# Logging_Controller.net
KiCad netlist of a schematic drawn in EAGLE
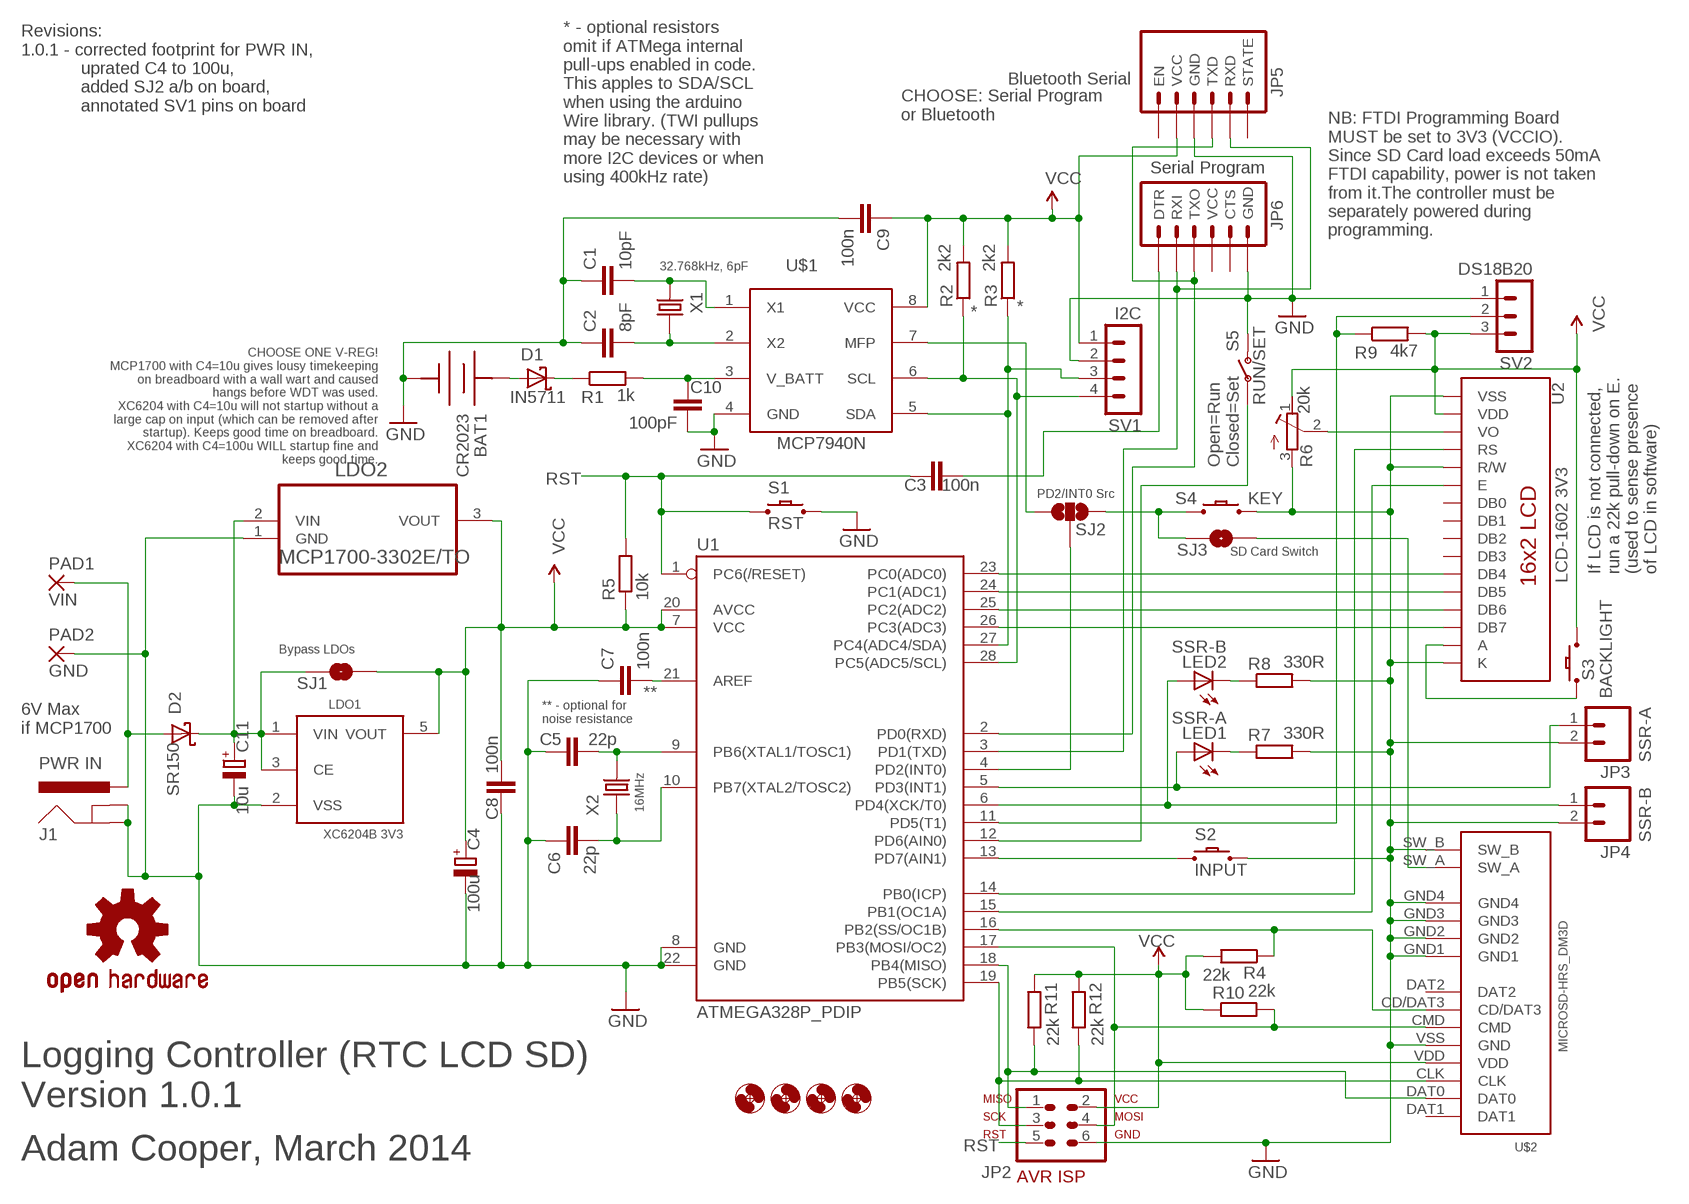
[diagram p0: schematic, sheet 1]

(export (version "E")
  (design (tool "Eeschema 10.0.6"))
  (components
    (comp (ref "BAT1")
      (value "CR2023")
      (footprint "eagle-import:KEYSTONE3003")
      (libsource (lib "eagle-import") (part "COIN-CELLLIR2450-H"))
    )
    (comp (ref "C1")
      (value "10pF")
      (footprint "eagle-import:C025-024X044")
      (libsource (lib "eagle-import") (part "C-EU025-024X044100NF+22PF"))
    )
    (comp (ref "C2")
      (value "8pF")
      (footprint "eagle-import:C025-024X044")
      (libsource (lib "eagle-import") (part "C-EU025-024X044100NF+22PF"))
    )
    (comp (ref "C3")
      (value "100n")
      (footprint "eagle-import:C025-024X044")
      (libsource (lib "eagle-import") (part "C-EU025-024X044100NF+22PF"))
    )
    (comp (ref "C4")
      (value "100u")
      (footprint "eagle-import:E2,5-5")
      (libsource (lib "eagle-import") (part "CPOL-EUE2.5-5"))
    )
    (comp (ref "C5")
      (value "22p")
      (footprint "eagle-import:C025-024X044")
      (libsource (lib "eagle-import") (part "C-EU025-024X044100NF+22PF"))
    )
    (comp (ref "C6")
      (value "22p")
      (footprint "eagle-import:C025-024X044")
      (libsource (lib "eagle-import") (part "C-EU025-024X044100NF+22PF"))
    )
    (comp (ref "C7")
      (value "100n")
      (footprint "eagle-import:C025-024X044")
      (libsource (lib "eagle-import") (part "C-EU025-024X044100NF+22PF"))
    )
    (comp (ref "C8")
      (value "100n")
      (footprint "eagle-import:C025-024X044")
      (libsource (lib "eagle-import") (part "C-EU025-024X044100NF+22PF"))
    )
    (comp (ref "C9")
      (value "100n")
      (footprint "eagle-import:C025-024X044")
      (libsource (lib "eagle-import") (part "C-EU025-024X044100NF+22PF"))
    )
    (comp (ref "C10")
      (value "100pF")
      (footprint "eagle-import:C025-024X044")
      (libsource (lib "eagle-import") (part "C-EU025-024X044100NF+22PF"))
    )
    (comp (ref "C11")
      (value "10u")
      (footprint "eagle-import:E2,5-5")
      (libsource (lib "eagle-import") (part "CPOL-EUE2.5-5"))
    )
    (comp (ref "D1")
      (value "IN5711")
      (footprint "eagle-import:DO35-7")
      (libsource (lib "eagle-import") (part "DIODE-SCHOTTKYDO35-7"))
    )
    (comp (ref "D2")
      (value "SR150")
      (footprint "eagle-import:DO-41")
      (libsource (lib "eagle-import") (part "DIODE-SCHOTTKYDO-41"))
    )
    (comp (ref "H1")
      (value "MOUNT-HOLE3.0_REDUCED")
      (footprint "eagle-import:3,0")
      (libsource (lib "eagle-import") (part "MOUNT-HOLE3.0_REDUCED"))
    )
    (comp (ref "H2")
      (value "MOUNT-HOLE3.0_REDUCED")
      (footprint "eagle-import:3,0")
      (libsource (lib "eagle-import") (part "MOUNT-HOLE3.0_REDUCED"))
    )
    (comp (ref "H3")
      (value "MOUNT-HOLE3.0_REDUCED")
      (footprint "eagle-import:3,0")
      (libsource (lib "eagle-import") (part "MOUNT-HOLE3.0_REDUCED"))
    )
    (comp (ref "H4")
      (value "MOUNT-HOLE3.0_REDUCED")
      (footprint "eagle-import:3,0")
      (libsource (lib "eagle-import") (part "MOUNT-HOLE3.0_REDUCED"))
    )
    (comp (ref "J1")
      (value "PWR IN")
      (footprint "eagle-import:POWER_JACK_SLOT2")
      (libsource (lib "eagle-import") (part "POWER_JACKMJ-179PH"))
    )
    (comp (ref "JP2")
      (value "AVR-ISP")
      (footprint "eagle-import:AVR-ISP-6")
      (libsource (lib "eagle-import") (part "AVR-ISP-6VERT"))
    )
    (comp (ref "JP3")
      (value "SSR-A")
      (footprint "eagle-import:1X02")
      (libsource (lib "eagle-import") (part "M02PTH"))
    )
    (comp (ref "JP4")
      (value "SSR-B")
      (footprint "eagle-import:1X02")
      (libsource (lib "eagle-import") (part "M02PTH"))
    )
    (comp (ref "JP5")
      (value "Bluetooth Serial")
      (footprint "eagle-import:BT_MOD_ROUND")
      (libsource (lib "eagle-import") (part "BLUETOOTH_SERIAL_MODULEBT_MOD_ROUND"))
    )
    (comp (ref "JP6")
      (value "Serial Program")
      (footprint "eagle-import:1X06")
      (libsource (lib "eagle-import") (part "ARDUINO_SERIAL_PROGRAMPTH"))
    )
    (comp (ref "LDO1")
      (value "XC6204B 3V3")
      (footprint "eagle-import:SOT23-5")
      (libsource (lib "eagle-import") (part "XC6204/5"))
    )
    (comp (ref "LDO2")
      (value "MCP1700-3302E/TO")
      (footprint "eagle-import:TO127P254X495-3")
      (libsource (lib "eagle-import") (part "MCP1700-3302E/TO"))
    )
    (comp (ref "LED1")
      (value "SSR-A")
      (footprint "eagle-import:LED5MM")
      (libsource (lib "eagle-import") (part "LED5MM"))
    )
    (comp (ref "LED2")
      (value "SSR-B")
      (footprint "eagle-import:LED5MM")
      (libsource (lib "eagle-import") (part "LED5MM"))
    )
    (comp (ref "LOGO1")
      (value "OSHW-LOGOS")
      (footprint "eagle-import:OSHW-LOGO-S")
      (libsource (lib "eagle-import") (part "OSHW-LOGOS"))
    )
    (comp (ref "PAD1")
      (value "VIN")
      (footprint "eagle-import:2,54_1,1")
      (libsource (lib "eagle-import") (part "WIREPAD2,54/1,1"))
    )
    (comp (ref "PAD2")
      (value "GND")
      (footprint "eagle-import:2,54_1,1")
      (libsource (lib "eagle-import") (part "WIREPAD2,54/1,1"))
    )
    (comp (ref "R1")
      (value "1k")
      (footprint "eagle-import:0204_7")
      (libsource (lib "eagle-import") (part "R-EU_0204/7"))
    )
    (comp (ref "R2")
      (value "2k2")
      (footprint "eagle-import:0204_7")
      (libsource (lib "eagle-import") (part "R-EU_0204/7"))
    )
    (comp (ref "R3")
      (value "2k2")
      (footprint "eagle-import:0204_7")
      (libsource (lib "eagle-import") (part "R-EU_0204/7"))
    )
    (comp (ref "R4")
      (value "22k")
      (footprint "eagle-import:0204_7")
      (libsource (lib "eagle-import") (part "R-EU_0204/7"))
    )
    (comp (ref "R5")
      (value "10k")
      (footprint "eagle-import:0204_7")
      (libsource (lib "eagle-import") (part "R-EU_0204/7"))
    )
    (comp (ref "R6")
      (value "20k")
      (footprint "eagle-import:RTRIMT93YB")
      (libsource (lib "eagle-import") (part "R-TRIMMT93YB"))
    )
    (comp (ref "R7")
      (value "330R")
      (footprint "eagle-import:0204_7")
      (libsource (lib "eagle-import") (part "R-EU_0204/7"))
    )
    (comp (ref "R8")
      (value "330R")
      (footprint "eagle-import:0204_7")
      (libsource (lib "eagle-import") (part "R-EU_0204/7"))
    )
    (comp (ref "R9")
      (value "4k7")
      (footprint "eagle-import:0204_7")
      (libsource (lib "eagle-import") (part "R-EU_0204/7"))
    )
    (comp (ref "R10")
      (value "22k")
      (footprint "eagle-import:0204_7")
      (libsource (lib "eagle-import") (part "R-EU_0204/7"))
    )
    (comp (ref "R11")
      (value "22k")
      (footprint "eagle-import:0204_7")
      (libsource (lib "eagle-import") (part "R-EU_0204/7"))
    )
    (comp (ref "R12")
      (value "22k")
      (footprint "eagle-import:0204_7")
      (libsource (lib "eagle-import") (part "R-EU_0204/7"))
    )
    (comp (ref "S1")
      (value "RST")
      (footprint "eagle-import:TACTILE-PTH")
      (libsource (lib "eagle-import") (part "SWITCH-MOMENTARY-2PTH"))
    )
    (comp (ref "S2")
      (value "INPUT")
      (footprint "eagle-import:OFF_BOARD_SPST")
      (libsource (lib "eagle-import") (part "SWITCH-MOMENTARY-2OFF_BOARD_SPST"))
    )
    (comp (ref "S3")
      (value "BACKLIGHT")
      (footprint "eagle-import:OFF_BOARD_SPST")
      (libsource (lib "eagle-import") (part "SWITCH-MOMENTARY-2OFF_BOARD_SPST"))
    )
    (comp (ref "S4")
      (value "KEY")
      (footprint "eagle-import:OFF_BOARD_SPST")
      (libsource (lib "eagle-import") (part "SWITCH-MOMENTARY-2OFF_BOARD_SPST"))
    )
    (comp (ref "S5")
      (value "RUN/SET")
      (footprint "eagle-import:SWITCH-SPST-OFFBOARD")
      (libsource (lib "eagle-import") (part "SWITCH-SPSTOFFBOARD"))
    )
    (comp (ref "SJ1")
      (value "Bypass LDOs")
      (footprint "eagle-import:SJ_2S-NO")
      (libsource (lib "eagle-import") (part "SOLDERJUMPERNO"))
    )
    (comp (ref "SJ2")
      (value "PD2/INT0 Src")
      (footprint "eagle-import:SJ_3")
      (libsource (lib "eagle-import") (part "SOLDERJUMPER_2WAYS"))
    )
    (comp (ref "SJ3")
      (value "SD Card Switch")
      (footprint "eagle-import:SJ_2S-NO")
      (libsource (lib "eagle-import") (part "SOLDERJUMPERNO"))
    )
    (comp (ref "SV1")
      (value "I2C")
      (footprint "eagle-import:MA04-1")
      (libsource (lib "eagle-import") (part "MA04-1"))
    )
    (comp (ref "SV2")
      (value "DS18B20")
      (footprint "eagle-import:MA03-1")
      (libsource (lib "eagle-import") (part "MA03-1"))
    )
    (comp (ref "U$1")
      (value "MCP7940N")
      (footprint "eagle-import:DIL08")
      (libsource (lib "eagle-import") (part "MCP7940NPDIP"))
    )
    (comp (ref "U$2")
      (value "MICROSD-HRS_DM3D")
      (footprint "eagle-import:DM3D")
      (libsource (lib "eagle-import") (part "MICROSD-HRS_DM3D"))
    )
    (comp (ref "U1")
      (value "ATMEGA328P_PDIP")
      (footprint "eagle-import:DIL28-3@1")
      (libsource (lib "eagle-import") (part "ATMEGA328P_PDIP"))
    )
    (comp (ref "U2")
      (value "LCD-1602 3V3")
      (footprint "eagle-import:LCD-16X2_NOSILK")
      (libsource (lib "eagle-import") (part "LCD-16X2NOSILK"))
    )
    (comp (ref "X1")
      (value "32.768kHz, 6pF")
      (footprint "eagle-import:TC26H")
      (libsource (lib "eagle-import") (part "CRYSTAL-TC26H"))
    )
    (comp (ref "X2")
      (value "16MHz")
      (footprint "eagle-import:HC49U-V")
      (libsource (lib "eagle-import") (part "CRYSTAL-HC49U-V16MHZ"))
    )
  )
  (nets
    (net (code "1") (name "/RST") (class "Default")
      (node (ref "C3") (pin "1") (pinfunction "1_1") (pintype "passive"))
      (node (ref "JP2") (pin "5") (pinfunction "5_5") (pintype "passive"))
      (node (ref "R5") (pin "2") (pinfunction "2_2") (pintype "passive"))
      (node (ref "S1") (pin "1") (pinfunction "1_1") (pintype "passive"))
      (node (ref "U1") (pin "1") (pinfunction "PC6(/RESET)_1") (pintype "bidirectional"))
    )
    (net (code "2") (name "GND") (class "Default")
      (node (ref "BAT1") (pin "NEG") (pinfunction "NEG_NEG") (pintype "bidirectional"))
      (node (ref "C1") (pin "1") (pinfunction "1_1") (pintype "passive"))
      (node (ref "C10") (pin "1") (pinfunction "1_1") (pintype "passive"))
      (node (ref "C11") (pin "-") (pinfunction "-_-") (pintype "passive"))
      (node (ref "C2") (pin "1") (pinfunction "1_1") (pintype "passive"))
      (node (ref "C4") (pin "-") (pinfunction "-_-") (pintype "passive"))
      (node (ref "C5") (pin "1") (pinfunction "1_1") (pintype "passive"))
      (node (ref "C6") (pin "1") (pinfunction "1_1") (pintype "passive"))
      (node (ref "C7") (pin "1") (pinfunction "1_1") (pintype "passive"))
      (node (ref "C8") (pin "1") (pinfunction "1_1") (pintype "passive"))
      (node (ref "C9") (pin "2") (pinfunction "2_2") (pintype "passive"))
      (node (ref "J1") (pin "GND") (pinfunction "GND_GND") (pintype "bidirectional"))
      (node (ref "J1") (pin "GND2") (pinfunction "GNDBREAK_GND2") (pintype "bidirectional"))
      (node (ref "JP2") (pin "6") (pinfunction "6_6") (pintype "passive"))
      (node (ref "JP3") (pin "2") (pinfunction "2_2") (pintype "passive"))
      (node (ref "JP4") (pin "2") (pinfunction "2_2") (pintype "passive"))
      (node (ref "JP5") (pin "4") (pinfunction "GND_4") (pintype "power_in"))
      (node (ref "JP6") (pin "6") (pinfunction "GND_6") (pintype "passive"))
      (node (ref "LDO1") (pin "2") (pinfunction "VSS_2") (pintype "power_in"))
      (node (ref "LDO2") (pin "1") (pinfunction "GND_1") (pintype "passive"))
      (node (ref "PAD2") (pin "1") (pinfunction "P_1") (pintype "passive"))
      (node (ref "R6") (pin "3") (pinfunction "E_3") (pintype "passive"))
      (node (ref "R7") (pin "2") (pinfunction "2_2") (pintype "passive"))
      (node (ref "R8") (pin "2") (pinfunction "2_2") (pintype "passive"))
      (node (ref "S1") (pin "3") (pinfunction "2_3") (pintype "passive"))
      (node (ref "S2") (pin "P$2") (pinfunction "2_P$2") (pintype "passive"))
      (node (ref "S4") (pin "P$2") (pinfunction "2_P$2") (pintype "passive"))
      (node (ref "S5") (pin "1") (pinfunction "O_1") (pintype "passive"))
      (node (ref "SV1") (pin "2") (pinfunction "2_2") (pintype "passive"))
      (node (ref "SV2") (pin "1") (pinfunction "1_1") (pintype "passive"))
      (node (ref "U$1") (pin "4") (pinfunction "GND_4") (pintype "bidirectional"))
      (node (ref "U$2") (pin "GND1") (pinfunction "GND1_GND1") (pintype "bidirectional"))
      (node (ref "U$2") (pin "GND2") (pinfunction "GND2_GND2") (pintype "bidirectional"))
      (node (ref "U$2") (pin "GND3") (pinfunction "GND3_GND3") (pintype "bidirectional"))
      (node (ref "U$2") (pin "GND4") (pinfunction "GND4_GND4") (pintype "bidirectional"))
      (node (ref "U$2") (pin "SW_B") (pinfunction "SW_B_SW_B") (pintype "bidirectional"))
      (node (ref "U$2") (pin "VSS") (pinfunction "GND_VSS") (pintype "bidirectional"))
      (node (ref "U1") (pin "22") (pinfunction "GND_22") (pintype "bidirectional"))
      (node (ref "U1") (pin "8") (pinfunction "GND_8") (pintype "bidirectional"))
      (node (ref "U2") (pin "1") (pinfunction "VSS_1") (pintype "power_in"))
      (node (ref "U2") (pin "16") (pinfunction "K_16") (pintype "power_in"))
      (node (ref "U2") (pin "5") (pinfunction "R/W_5") (pintype "input"))
    )
    (net (code "3") (name "Net-(BAT1-POS-PadPOS1)") (class "Default")
      (node (ref "BAT1") (pin "POS") (pinfunction "POS_POS") (pintype "bidirectional"))
      (node (ref "BAT1") (pin "POS1") (pinfunction "POS_POS1") (pintype "bidirectional"))
      (node (ref "D1") (pin "A") (pinfunction "A_A") (pintype "passive"))
    )
    (net (code "4") (name "Net-(D1-PadC)") (class "Default")
      (node (ref "D1") (pin "C") (pinfunction "C_C") (pintype "passive"))
      (node (ref "R1") (pin "1") (pinfunction "1_1") (pintype "passive"))
    )
    (net (code "5") (name "Net-(J1-PWR)") (class "Default")
      (node (ref "D2") (pin "A") (pinfunction "A_A") (pintype "passive"))
      (node (ref "J1") (pin "POS") (pinfunction "PWR_POS") (pintype "bidirectional"))
      (node (ref "PAD1") (pin "1") (pinfunction "P_1") (pintype "passive"))
    )
    (net (code "6") (name "Net-(JP5-RXD)") (class "Default")
      (node (ref "JP5") (pin "2") (pinfunction "RXD_2") (pintype "input"))
      (node (ref "JP6") (pin "2") (pinfunction "RXI_2") (pintype "passive"))
      (node (ref "U1") (pin "3") (pinfunction "PD1(TXD)_3") (pintype "bidirectional"))
    )
    (net (code "7") (name "Net-(JP5-TXD)") (class "Default")
      (node (ref "JP5") (pin "3") (pinfunction "TXD_3") (pintype "output"))
      (node (ref "JP6") (pin "3") (pinfunction "TXO_3") (pintype "passive"))
      (node (ref "U1") (pin "2") (pinfunction "PD0(RXD)_2") (pintype "bidirectional"))
    )
    (net (code "8") (name "Net-(JP6-DTR)") (class "Default")
      (node (ref "C3") (pin "2") (pinfunction "2_2") (pintype "passive"))
      (node (ref "JP6") (pin "1") (pinfunction "DTR_1") (pintype "passive"))
    )
    (net (code "9") (name "Net-(LDO1-CE)") (class "Default")
      (node (ref "C11") (pin "+") (pinfunction "+_+") (pintype "passive"))
      (node (ref "D2") (pin "C") (pinfunction "C_C") (pintype "passive"))
      (node (ref "LDO1") (pin "1") (pinfunction "VIN_1") (pintype "power_in"))
      (node (ref "LDO1") (pin "3") (pinfunction "CE_3") (pintype "input"))
      (node (ref "LDO2") (pin "2") (pinfunction "VIN_2") (pintype "input"))
      (node (ref "SJ1") (pin "1") (pinfunction "1_1") (pintype "passive"))
    )
    (net (code "10") (name "Net-(LED1-C)") (class "Default")
      (node (ref "LED1") (pin "K") (pinfunction "C_K") (pintype "passive"))
      (node (ref "R7") (pin "1") (pinfunction "1_1") (pintype "passive"))
    )
    (net (code "11") (name "Net-(LED2-C)") (class "Default")
      (node (ref "LED2") (pin "K") (pinfunction "C_K") (pintype "passive"))
      (node (ref "R8") (pin "1") (pinfunction "1_1") (pintype "passive"))
    )
    (net (code "12") (name "Net-(R6-S)") (class "Default")
      (node (ref "R6") (pin "2") (pinfunction "S_2") (pintype "passive"))
      (node (ref "U2") (pin "3") (pinfunction "VO_3") (pintype "bidirectional"))
    )
    (net (code "13") (name "Net-(S2-1)") (class "Default")
      (node (ref "S2") (pin "P$1") (pinfunction "1_P$1") (pintype "passive"))
      (node (ref "U1") (pin "13") (pinfunction "PD7(AIN1)_13") (pintype "bidirectional"))
    )
    (net (code "14") (name "Net-(S3-1)") (class "Default")
      (node (ref "S3") (pin "P$1") (pinfunction "1_P$1") (pintype "passive"))
      (node (ref "U2") (pin "15") (pinfunction "A_15") (pintype "power_in"))
    )
    (net (code "15") (name "Net-(S4-1)") (class "Default")
      (node (ref "S4") (pin "P$1") (pinfunction "1_P$1") (pintype "passive"))
      (node (ref "SJ2") (pin "3") (pinfunction "3_3") (pintype "passive"))
      (node (ref "SJ3") (pin "1") (pinfunction "1_1") (pintype "passive"))
    )
    (net (code "16") (name "Net-(S5-P)") (class "Default")
      (node (ref "S5") (pin "2") (pinfunction "P_2") (pintype "passive"))
      (node (ref "U1") (pin "12") (pinfunction "PD6(AIN0)_12") (pintype "bidirectional"))
    )
    (net (code "17") (name "Net-(SJ3-Pad2)") (class "Default")
      (node (ref "SJ3") (pin "2") (pinfunction "2_2") (pintype "passive"))
      (node (ref "U$2") (pin "SW_A") (pinfunction "SW_A_SW_A") (pintype "bidirectional"))
    )
    (net (code "18") (name "Net-(U$1-MFP)") (class "Default")
      (node (ref "SJ2") (pin "1") (pinfunction "1_1") (pintype "passive"))
      (node (ref "U$1") (pin "7") (pinfunction "MFP_7") (pintype "bidirectional"))
    )
    (net (code "19") (name "Net-(U$1-SCL)") (class "Default")
      (node (ref "R2") (pin "1") (pinfunction "1_1") (pintype "passive"))
      (node (ref "SV1") (pin "4") (pinfunction "4_4") (pintype "passive"))
      (node (ref "U$1") (pin "6") (pinfunction "SCL_6") (pintype "bidirectional"))
      (node (ref "U1") (pin "28") (pinfunction "PC5(ADC5/SCL)_28") (pintype "bidirectional"))
    )
    (net (code "20") (name "Net-(U$1-SDA)") (class "Default")
      (node (ref "R3") (pin "1") (pinfunction "1_1") (pintype "passive"))
      (node (ref "SV1") (pin "3") (pinfunction "3_3") (pintype "passive"))
      (node (ref "U$1") (pin "5") (pinfunction "SDA_5") (pintype "bidirectional"))
      (node (ref "U1") (pin "27") (pinfunction "PC4(ADC4/SDA)_27") (pintype "bidirectional"))
    )
    (net (code "21") (name "Net-(U$1-V_BATT)") (class "Default")
      (node (ref "C10") (pin "2") (pinfunction "2_2") (pintype "passive"))
      (node (ref "R1") (pin "2") (pinfunction "2_2") (pintype "passive"))
      (node (ref "U$1") (pin "3") (pinfunction "V_BATT_3") (pintype "bidirectional"))
    )
    (net (code "22") (name "Net-(U$1-X1)") (class "Default")
      (node (ref "C1") (pin "2") (pinfunction "2_2") (pintype "passive"))
      (node (ref "U$1") (pin "1") (pinfunction "X1_1") (pintype "bidirectional"))
      (node (ref "X1") (pin "2") (pinfunction "2_2") (pintype "passive"))
    )
    (net (code "23") (name "Net-(U$1-X2)") (class "Default")
      (node (ref "C2") (pin "2") (pinfunction "2_2") (pintype "passive"))
      (node (ref "U$1") (pin "2") (pinfunction "X2_2") (pintype "bidirectional"))
      (node (ref "X1") (pin "1") (pinfunction "1_1") (pintype "passive"))
    )
    (net (code "24") (name "Net-(U1-AREF)") (class "Default")
      (node (ref "C7") (pin "2") (pinfunction "2_2") (pintype "passive"))
      (node (ref "U1") (pin "21") (pinfunction "AREF_21") (pintype "bidirectional"))
    )
    (net (code "25") (name "Net-(U1-PB0(ICP))") (class "Default")
      (node (ref "U1") (pin "14") (pinfunction "PB0(ICP)_14") (pintype "bidirectional"))
      (node (ref "U2") (pin "4") (pinfunction "RS_4") (pintype "input"))
    )
    (net (code "26") (name "Net-(U1-PB1(OC1A))") (class "Default")
      (node (ref "U1") (pin "15") (pinfunction "PB1(OC1A)_15") (pintype "bidirectional"))
      (node (ref "U2") (pin "6") (pinfunction "E_6") (pintype "input"))
    )
    (net (code "27") (name "Net-(U1-PB2(SS{slash}OC1B))") (class "Default")
      (node (ref "R4") (pin "1") (pinfunction "1_1") (pintype "passive"))
      (node (ref "U$2") (pin "CD/DAT3") (pinfunction "CD/DAT3_CD/DAT3") (pintype "bidirectional"))
      (node (ref "U1") (pin "16") (pinfunction "PB2(SS/OC1B)_16") (pintype "bidirectional"))
    )
    (net (code "28") (name "Net-(U1-PB3(MOSI{slash}OC2))") (class "Default")
      (node (ref "JP2") (pin "4") (pinfunction "4_4") (pintype "passive"))
      (node (ref "R10") (pin "2") (pinfunction "2_2") (pintype "passive"))
      (node (ref "U$2") (pin "CMD") (pinfunction "CMD_CMD") (pintype "bidirectional"))
      (node (ref "U1") (pin "17") (pinfunction "PB3(MOSI/OC2)_17") (pintype "bidirectional"))
    )
    (net (code "29") (name "Net-(U1-PB4(MISO))") (class "Default")
      (node (ref "JP2") (pin "1") (pinfunction "1_1") (pintype "passive"))
      (node (ref "R11") (pin "2") (pinfunction "2_2") (pintype "passive"))
      (node (ref "U$2") (pin "DAT0") (pinfunction "DAT0_DAT0") (pintype "bidirectional"))
      (node (ref "U1") (pin "18") (pinfunction "PB4(MISO)_18") (pintype "bidirectional"))
    )
    (net (code "30") (name "Net-(U1-PB5(SCK))") (class "Default")
      (node (ref "JP2") (pin "3") (pinfunction "3_3") (pintype "passive"))
      (node (ref "R12") (pin "2") (pinfunction "2_2") (pintype "passive"))
      (node (ref "U$2") (pin "CLK") (pinfunction "CLK_CLK") (pintype "bidirectional"))
      (node (ref "U1") (pin "19") (pinfunction "PB5(SCK)_19") (pintype "bidirectional"))
    )
    (net (code "31") (name "Net-(U1-PB6(XTAL1{slash}TOSC1))") (class "Default")
      (node (ref "C5") (pin "2") (pinfunction "2_2") (pintype "passive"))
      (node (ref "U1") (pin "9") (pinfunction "PB6(XTAL1/TOSC1)_9") (pintype "bidirectional"))
      (node (ref "X2") (pin "2") (pinfunction "2_2") (pintype "passive"))
    )
    (net (code "32") (name "Net-(U1-PB7(XTAL2{slash}TOSC2))") (class "Default")
      (node (ref "C6") (pin "2") (pinfunction "2_2") (pintype "passive"))
      (node (ref "U1") (pin "10") (pinfunction "PB7(XTAL2/TOSC2)_10") (pintype "bidirectional"))
      (node (ref "X2") (pin "1") (pinfunction "1_1") (pintype "passive"))
    )
    (net (code "33") (name "Net-(U1-PC0(ADC0))") (class "Default")
      (node (ref "U1") (pin "23") (pinfunction "PC0(ADC0)_23") (pintype "bidirectional"))
      (node (ref "U2") (pin "11") (pinfunction "DB4_11") (pintype "bidirectional"))
    )
    (net (code "34") (name "Net-(U1-PC1(ADC1))") (class "Default")
      (node (ref "U1") (pin "24") (pinfunction "PC1(ADC1)_24") (pintype "bidirectional"))
      (node (ref "U2") (pin "12") (pinfunction "DB5_12") (pintype "bidirectional"))
    )
    (net (code "35") (name "Net-(U1-PC2(ADC2))") (class "Default")
      (node (ref "U1") (pin "25") (pinfunction "PC2(ADC2)_25") (pintype "bidirectional"))
      (node (ref "U2") (pin "13") (pinfunction "DB6_13") (pintype "bidirectional"))
    )
    (net (code "36") (name "Net-(U1-PC3(ADC3))") (class "Default")
      (node (ref "U1") (pin "26") (pinfunction "PC3(ADC3)_26") (pintype "bidirectional"))
      (node (ref "U2") (pin "14") (pinfunction "DB7_14") (pintype "bidirectional"))
    )
    (net (code "37") (name "Net-(U1-PD2(INT0))") (class "Default")
      (node (ref "SJ2") (pin "2") (pinfunction "2_2") (pintype "passive"))
      (node (ref "U1") (pin "4") (pinfunction "PD2(INT0)_4") (pintype "bidirectional"))
    )
    (net (code "38") (name "Net-(U1-PD3(INT1))") (class "Default")
      (node (ref "JP3") (pin "1") (pinfunction "1_1") (pintype "passive"))
      (node (ref "LED1") (pin "A") (pinfunction "A_A") (pintype "passive"))
      (node (ref "U1") (pin "5") (pinfunction "PD3(INT1)_5") (pintype "bidirectional"))
    )
    (net (code "39") (name "Net-(U1-PD4(XCK{slash}T0))") (class "Default")
      (node (ref "JP4") (pin "1") (pinfunction "1_1") (pintype "passive"))
      (node (ref "LED2") (pin "A") (pinfunction "A_A") (pintype "passive"))
      (node (ref "U1") (pin "6") (pinfunction "PD4(XCK/T0)_6") (pintype "bidirectional"))
    )
    (net (code "40") (name "Net-(U1-PD5(T1))") (class "Default")
      (node (ref "R9") (pin "1") (pinfunction "1_1") (pintype "passive"))
      (node (ref "SV2") (pin "2") (pinfunction "2_2") (pintype "passive"))
      (node (ref "U1") (pin "11") (pinfunction "PD5(T1)_11") (pintype "bidirectional"))
    )
    (net (code "41") (name "VCC") (class "Default")
      (node (ref "C4") (pin "+") (pinfunction "+_+") (pintype "passive"))
      (node (ref "C8") (pin "2") (pinfunction "2_2") (pintype "passive"))
      (node (ref "C9") (pin "1") (pinfunction "1_1") (pintype "passive"))
      (node (ref "JP2") (pin "2") (pinfunction "2_2") (pintype "passive"))
      (node (ref "JP5") (pin "5") (pinfunction "VCC_5") (pintype "power_in"))
      (node (ref "LDO1") (pin "5") (pinfunction "VOUT_5") (pintype "power_in"))
      (node (ref "LDO2") (pin "3") (pinfunction "VOUT_3") (pintype "output"))
      (node (ref "R10") (pin "1") (pinfunction "1_1") (pintype "passive"))
      (node (ref "R11") (pin "1") (pinfunction "1_1") (pintype "passive"))
      (node (ref "R12") (pin "1") (pinfunction "1_1") (pintype "passive"))
      (node (ref "R2") (pin "2") (pinfunction "2_2") (pintype "passive"))
      (node (ref "R3") (pin "2") (pinfunction "2_2") (pintype "passive"))
      (node (ref "R4") (pin "2") (pinfunction "2_2") (pintype "passive"))
      (node (ref "R5") (pin "1") (pinfunction "1_1") (pintype "passive"))
      (node (ref "R6") (pin "1") (pinfunction "A_1") (pintype "passive"))
      (node (ref "R9") (pin "2") (pinfunction "2_2") (pintype "passive"))
      (node (ref "S3") (pin "P$2") (pinfunction "2_P$2") (pintype "passive"))
      (node (ref "SJ1") (pin "2") (pinfunction "2_2") (pintype "passive"))
      (node (ref "SV1") (pin "1") (pinfunction "1_1") (pintype "passive"))
      (node (ref "SV2") (pin "3") (pinfunction "3_3") (pintype "passive"))
      (node (ref "U$1") (pin "8") (pinfunction "VCC_8") (pintype "bidirectional"))
      (node (ref "U$2") (pin "VDD") (pinfunction "VDD_VDD") (pintype "bidirectional"))
      (node (ref "U1") (pin "20") (pinfunction "AVCC_20") (pintype "bidirectional"))
      (node (ref "U1") (pin "7") (pinfunction "VCC_7") (pintype "bidirectional"))
      (node (ref "U2") (pin "2") (pinfunction "VDD_2") (pintype "power_in"))
    )
    (net (code "42") (name "unconnected-(JP5-EN-Pad6)") (class "Default")
      (node (ref "JP5") (pin "6") (pinfunction "EN_6") (pintype "input"))
    )
    (net (code "43") (name "unconnected-(JP5-STATE-Pad1)") (class "Default")
      (node (ref "JP5") (pin "1") (pinfunction "STATE_1") (pintype "input"))
    )
    (net (code "44") (name "unconnected-(JP6-CTS-Pad5)") (class "Default")
      (node (ref "JP6") (pin "5") (pinfunction "CTS_5") (pintype "passive"))
    )
    (net (code "45") (name "unconnected-(JP6-VCC-Pad4)") (class "Default")
      (node (ref "JP6") (pin "4") (pinfunction "VCC_4") (pintype "passive"))
    )
    (net (code "46") (name "unconnected-(U$2-PadDAT1)") (class "Default")
      (node (ref "U$2") (pin "DAT1") (pinfunction "DAT1_DAT1") (pintype "bidirectional"))
    )
    (net (code "47") (name "unconnected-(U$2-PadDAT2)") (class "Default")
      (node (ref "U$2") (pin "DAT2") (pinfunction "DAT2_DAT2") (pintype "bidirectional"))
    )
    (net (code "48") (name "unconnected-(U2-DB0-Pad7)") (class "Default")
      (node (ref "U2") (pin "7") (pinfunction "DB0_7") (pintype "bidirectional"))
    )
    (net (code "49") (name "unconnected-(U2-DB1-Pad8)") (class "Default")
      (node (ref "U2") (pin "8") (pinfunction "DB1_8") (pintype "bidirectional"))
    )
    (net (code "50") (name "unconnected-(U2-DB2-Pad9)") (class "Default")
      (node (ref "U2") (pin "9") (pinfunction "DB2_9") (pintype "bidirectional"))
    )
    (net (code "51") (name "unconnected-(U2-DB3-Pad10)") (class "Default")
      (node (ref "U2") (pin "10") (pinfunction "DB3_10") (pintype "bidirectional"))
    )
  )
)
